# 1_PSU.net
KiCad netlist of a schematic drawn in Altium Designer
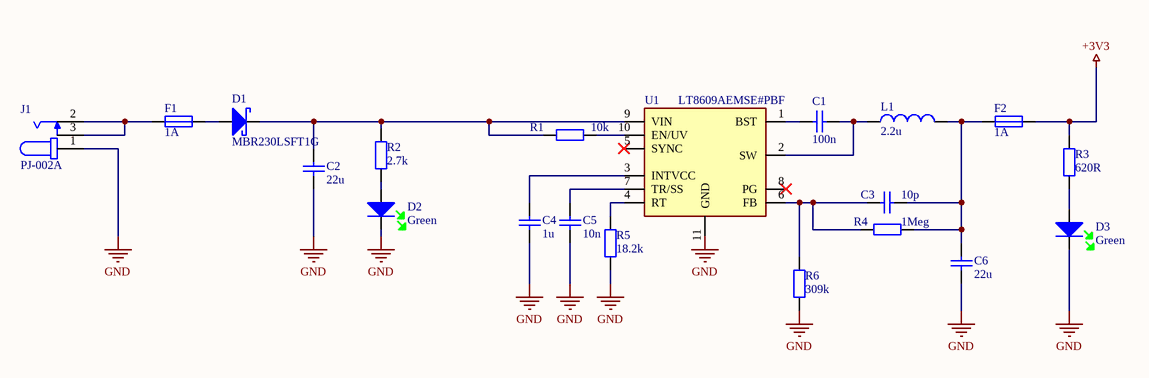
[diagram p0: [1] PSU.SchDoc]

(export (version "E")
  (design (tool "Eeschema 10.0.6"))
  (components
    (comp (ref "C1")
      (value "100n")
      (footprint "STguitar:Capacitor 0603")
      (description "Multilayer Ceramic Capacitors MLCC - SMD/SMT 0603 16VDC 0.1uF 10% X7R")
      (fields
        (field (name "MANUFACTURER PART NUMBER") "EMK107B7104KA-T")
        (field (name "MANUFACTURER") "Taiyo Yuden")
      )
      (libsource (lib "STguitar") (part "Capacitor 100n 10% 0603 EMK107B7104KA-T"))
    )
    (comp (ref "C2")
      (value "22u")
      (footprint "STguitar:Capacitor 0603")
      (description "Multilayer Ceramic Capacitors MLCC - SMD/SMT 22uF+/-20% 16V X5R 1608")
      (fields
        (field (name "MANUFACTURER PART NUMBER") "CL10A226MO7JZNC")
        (field (name "MANUFACTURER") "Samsung Electro-Mechanics")
      )
      (libsource (lib "STguitar") (part "Capacitor 22u 10% 0603 CL10A226MO7JZNC"))
    )
    (comp (ref "C3")
      (value "10p")
      (footprint "STguitar:Capacitor 0603")
      (description "Multilayer Ceramic Capacitors MLCC - SMD/SMT 16V 10pF X7R 0603 10%")
      (fields (field (name "MANUFACTURER PART NUMBER") "0603YC100KAT2A") (field (name "MANUFACTURER") "AVX"))
      (libsource (lib "STguitar") (part "Capacitor 10p 10% 0603 0603YC100KAT2A"))
    )
    (comp (ref "C4")
      (value "1u")
      (footprint "STguitar:Capacitor 0603")
      (description "Multilayer Ceramic Capacitors MLCC - SMD/SMT 0603 16VDC 1uF 10% X7R")
      (fields
        (field (name "MANUFACTURER PART NUMBER") "EMK107B7105KA-T")
        (field (name "MANUFACTURER") "Taiyo Yuden")
      )
      (libsource (lib "STguitar") (part "Capacitor 1u 10% 0603 EMK107B7105KA-T"))
    )
    (comp (ref "C5")
      (value "10n")
      (footprint "STguitar:Capacitor 0603")
      (description "Multilayer Ceramic Capacitors MLCC - SMD/SMT 0603 16VDC 10nF 10% Low Distort")
      (fields
        (field (name "MANUFACTURER PART NUMBER") "EMK107SD103KA-T")
        (field (name "MANUFACTURER") "Taiyo Yuden")
      )
      (libsource (lib "STguitar") (part "Capacitor 10n 10% 0603 EMK107SD103KA-T"))
    )
    (comp (ref "C6")
      (value "22u")
      (footprint "STguitar:Capacitor 0603")
      (description "Multilayer Ceramic Capacitors MLCC - SMD/SMT 22uF+/-20% 16V X5R 1608")
      (fields
        (field (name "MANUFACTURER PART NUMBER") "CL10A226MO7JZNC")
        (field (name "MANUFACTURER") "Samsung Electro-Mechanics")
      )
      (libsource (lib "STguitar") (part "Capacitor 22u 10% 0603 CL10A226MO7JZNC"))
    )
    (comp (ref "D1")
      (value "MBR230LSFT1G")
      (footprint "STguitar:Diode SOD123f")
      (description "Schottky Diodes & Rectifiers 2A 30V SCHOTTKY")
      (fields (field (name "MANUFACTURER") "ON Semiconductor / Fairchild"))
      (libsource (lib "STguitar") (part "Diode Schottky Diodes2A 30V SCHOTTKY MBR230LSFT1G"))
    )
    (comp (ref "D2")
      (value "Green")
      (footprint "STguitar:LED 0805 Green")
      (description "Standard LEDs - SMD 0805 Dome Lens LED Green- 570nm")
      (fields
        (field (name "MANUFACTURER PART NUMBER") "APTD2012LCGCK")
        (field (name "MANUFACTURER") "Kingbright")
      )
      (libsource (lib "STguitar") (part "Diode Standard LEDs - SMD 0805 Dome Lens LED Green- 570nm APTD2012LCGCK"))
    )
    (comp (ref "D3")
      (value "Green")
      (footprint "STguitar:LED 0805 Green")
      (description "Standard LEDs - SMD 0805 Dome Lens LED Green- 570nm")
      (fields
        (field (name "MANUFACTURER PART NUMBER") "APTD2012LCGCK")
        (field (name "MANUFACTURER") "Kingbright")
      )
      (libsource (lib "STguitar") (part "Diode Standard LEDs - SMD 0805 Dome Lens LED Green- 570nm APTD2012LCGCK"))
    )
    (comp (ref "F1")
      (value "1A")
      (footprint "STguitar:Fuse 1206")
      (description "Surface Mount Fuses 1206 SMT Fuse Fast Acting, 1A")
      (fields (field (name "MANUFACTURER PART NUMBER") "C1F 1") (field (name "MANUFACTURER") "Bel Fuse"))
      (libsource (lib "STguitar") (part "Fuse 1206 SMT Fuse Fast Acting, 1A"))
    )
    (comp (ref "F2")
      (value "1A")
      (footprint "STguitar:Fuse 1206")
      (description "Surface Mount Fuses 1206 SMT Fuse Fast Acting, 1A")
      (fields (field (name "MANUFACTURER PART NUMBER") "C1F 1") (field (name "MANUFACTURER") "Bel Fuse"))
      (libsource (lib "STguitar") (part "Fuse 1206 SMT Fuse Fast Acting, 1A"))
    )
    (comp (ref "J1")
      (value "PJ-002A")
      (footprint "STguitar:Mechanical CUI_PJ-002A")
      (description "DC Power Connectors Power Jacks")
      (fields (field (name "MANUFACTURER") "https://pl.mouser.com/datasheet/2/670/pj_002a-1778764.pdf"))
      (libsource (lib "STguitar") (part "Mechanical DC Power Connectors Power Jacks"))
    )
    (comp (ref "L1")
      (value "2.2u")
      (footprint "STguitar:Inductor XAL50xx")
      (description "Fixed Inductors 2.2uH Shld 20% 9.2A 14.5mOhms AECQ2")
      (fields
        (field (name "MANUFACTURER PART NUMBER") "XAL5030-222MEB")
        (field (name "MANUFACTURER") "Coilcraft")
      )
      (libsource (lib "STguitar") (part "Inductor Fixed Inductors 2.2uH Shld 20% 9.2A 14.5mOhms AECQ2"))
    )
    (comp (ref "R1")
      (value "10k")
      (footprint "STguitar:Resistor 0603")
      (description "Thin Film Resistors - SMD 10K ohm 1% 1/10W")
      (fields
        (field (name "MANUFACTURER PART NUMBER") "RT0603FRE0710KL")
        (field (name "MANUFACTURER") "Yageo")
      )
      (libsource (lib "STguitar") (part "Resistor 10k 1% 0603 RT0603FRE0710KL"))
    )
    (comp (ref "R2")
      (value "2.7k")
      (footprint "STguitar:Resistor 0603")
      (description "Thin Film Resistors - SMD 1/10W 2.7K ohm 1% 50ppm")
      (fields
        (field (name "MANUFACTURER PART NUMBER") "RT0603FRE072K7L")
        (field (name "MANUFACTURER") "Yageo")
      )
      (libsource (lib "STguitar") (part "Resistor 2.7k 1% 0603 RT0603FRE072K7L"))
    )
    (comp (ref "R3")
      (value "620R")
      (footprint "STguitar:Resistor 0603")
      (description "Thin Film Resistors - SMD 620 OHM 1% 50PPM 1/10W")
      (fields
        (field (name "MANUFACTURER PART NUMBER") "RT0603FRE07620RL")
        (field (name "MANUFACTURER") "Yageo")
      )
      (libsource (lib "STguitar") (part "Resistor 620R 1% 0603 RT0603FRE07620RL"))
    )
    (comp (ref "R4")
      (value "1Meg")
      (footprint "STguitar:Resistor 0603")
      (description "Thin Film Resistors - SMD 1M OHM 1% 50PPM 1/10W")
      (fields
        (field (name "MANUFACTURER PART NUMBER") "RT0603FRE071ML")
        (field (name "MANUFACTURER") "Yageo")
      )
      (libsource (lib "STguitar") (part "Resistor 1Meg 1% 0603 RT0603FRE071ML"))
    )
    (comp (ref "R5")
      (value "18.2k")
      (footprint "STguitar:Resistor 0603")
      (description "Thin Film Resistors - SMD 1/10W 18.2K ohm 1% 50ppm")
      (fields
        (field (name "MANUFACTURER PART NUMBER") "RT0603FRE0718K2L")
        (field (name "MANUFACTURER") "Yageo")
      )
      (libsource (lib "STguitar") (part "Resistor 18.2k 1% 0603 RT0603FRE0718K2L"))
    )
    (comp (ref "R6")
      (value "309k")
      (footprint "STguitar:Resistor 0603")
      (description "Thin Film Resistors - SMD 1/10W 309K ohm 1% 50ppm")
      (fields
        (field (name "MANUFACTURER PART NUMBER") "RT0603FRE07309KL")
        (field (name "MANUFACTURER") "Yageo")
      )
      (libsource (lib "STguitar") (part "Resistor 309k 1% 0603 RT0603FRE07309KL"))
    )
    (comp (ref "U1")
      (value "LT8609AEMSE#PBF")
      (footprint "STguitar:MSOP-10")
      (description "Switching Voltage Regulators 42V, 2A Synchronous Step-Down Regulator with 2.5uA Quiescent Current")
      (fields (field (name "MANUFACTURER") "Analog Devices"))
      (libsource (lib "STguitar") (part "IC Switching Voltage Regulators 42V, 2A/3A Peak Sync Buck Reg w/ 2.5uA LT8609AEMSE#PBF"))
    )
  )
  (nets
    (net (code "1") (name "+3V3") (class "Default")
      (node (ref "F2") (pin "2") (pinfunction "2_2") (pintype "passive"))
      (node (ref "R3") (pin "2") (pinfunction "2_2") (pintype "passive"))
    )
    (net (code "2") (name "GND") (class "Default")
      (node (ref "C2") (pin "1") (pinfunction "1_1") (pintype "passive"))
      (node (ref "C4") (pin "1") (pinfunction "1_1") (pintype "passive"))
      (node (ref "C5") (pin "1") (pinfunction "1_1") (pintype "passive"))
      (node (ref "C6") (pin "1") (pinfunction "1_1") (pintype "passive"))
      (node (ref "D2") (pin "1") (pinfunction "1_1") (pintype "passive"))
      (node (ref "D3") (pin "1") (pinfunction "1_1") (pintype "passive"))
      (node (ref "J1") (pin "1") (pinfunction "1_1") (pintype "passive"))
      (node (ref "R5") (pin "1") (pinfunction "1_1") (pintype "passive"))
      (node (ref "R6") (pin "1") (pinfunction "1_1") (pintype "passive"))
      (node (ref "U1") (pin "11") (pinfunction "GND_11") (pintype "passive"))
    )
    (net (code "3") (name "Net-(C3-Pad2)") (class "Default")
      (node (ref "C3") (pin "2") (pinfunction "2_2") (pintype "passive"))
      (node (ref "C6") (pin "2") (pinfunction "2_2") (pintype "passive"))
      (node (ref "F2") (pin "1") (pinfunction "1_1") (pintype "passive"))
      (node (ref "L1") (pin "2") (pinfunction "2_2") (pintype "passive"))
      (node (ref "R4") (pin "2") (pinfunction "2_2") (pintype "passive"))
    )
    (net (code "4") (name "Net-(D1-Pad1)") (class "Default")
      (node (ref "D1") (pin "1") (pinfunction "1_1") (pintype "passive"))
      (node (ref "F1") (pin "2") (pinfunction "2_2") (pintype "passive"))
    )
    (net (code "5") (name "Net-(D2-Pad2)") (class "Default")
      (node (ref "D2") (pin "2") (pinfunction "2_2") (pintype "passive"))
      (node (ref "R2") (pin "1") (pinfunction "1_1") (pintype "passive"))
    )
    (net (code "6") (name "Net-(D3-Pad2)") (class "Default")
      (node (ref "D3") (pin "2") (pinfunction "2_2") (pintype "passive"))
      (node (ref "R3") (pin "1") (pinfunction "1_1") (pintype "passive"))
    )
    (net (code "7") (name "Net-(F1-Pad1)") (class "Default")
      (node (ref "F1") (pin "1") (pinfunction "1_1") (pintype "passive"))
      (node (ref "J1") (pin "2") (pinfunction "2_2") (pintype "passive"))
      (node (ref "J1") (pin "3") (pinfunction "3_3") (pintype "passive"))
    )
    (net (code "8") (name "Net-(U1-BST)") (class "Default")
      (node (ref "C1") (pin "1") (pinfunction "1_1") (pintype "passive"))
      (node (ref "U1") (pin "1") (pinfunction "BST_1") (pintype "passive"))
    )
    (net (code "9") (name "Net-(U1-EN{slash}UV)") (class "Default")
      (node (ref "R1") (pin "2") (pinfunction "2_2") (pintype "passive"))
      (node (ref "U1") (pin "10") (pinfunction "EN/UV_10") (pintype "passive"))
    )
    (net (code "10") (name "Net-(U1-FB)") (class "Default")
      (node (ref "C3") (pin "1") (pinfunction "1_1") (pintype "passive"))
      (node (ref "R4") (pin "1") (pinfunction "1_1") (pintype "passive"))
      (node (ref "R6") (pin "2") (pinfunction "2_2") (pintype "passive"))
      (node (ref "U1") (pin "6") (pinfunction "FB_6") (pintype "passive"))
    )
    (net (code "11") (name "Net-(U1-INTVCC)") (class "Default")
      (node (ref "C4") (pin "2") (pinfunction "2_2") (pintype "passive"))
      (node (ref "U1") (pin "3") (pinfunction "INTVCC_3") (pintype "passive"))
    )
    (net (code "12") (name "Net-(U1-RT)") (class "Default")
      (node (ref "R5") (pin "2") (pinfunction "2_2") (pintype "passive"))
      (node (ref "U1") (pin "4") (pinfunction "RT_4") (pintype "passive"))
    )
    (net (code "13") (name "Net-(U1-SW)") (class "Default")
      (node (ref "C1") (pin "2") (pinfunction "2_2") (pintype "passive"))
      (node (ref "L1") (pin "1") (pinfunction "1_1") (pintype "passive"))
      (node (ref "U1") (pin "2") (pinfunction "SW_2") (pintype "passive"))
    )
    (net (code "14") (name "Net-(U1-TR{slash}SS)") (class "Default")
      (node (ref "C5") (pin "2") (pinfunction "2_2") (pintype "passive"))
      (node (ref "U1") (pin "7") (pinfunction "TR/SS_7") (pintype "passive"))
    )
    (net (code "15") (name "Net-(U1-VIN)") (class "Default")
      (node (ref "C2") (pin "2") (pinfunction "2_2") (pintype "passive"))
      (node (ref "D1") (pin "2") (pinfunction "2_2") (pintype "passive"))
      (node (ref "R1") (pin "1") (pinfunction "1_1") (pintype "passive"))
      (node (ref "R2") (pin "2") (pinfunction "2_2") (pintype "passive"))
      (node (ref "U1") (pin "9") (pinfunction "VIN_9") (pintype "passive"))
    )
    (net (code "16") (name "unconnected-(U1-PG-Pad8)") (class "Default")
      (node (ref "U1") (pin "8") (pinfunction "PG_8") (pintype "passive+no_connect"))
    )
    (net (code "17") (name "unconnected-(U1-SYNC-Pad5)") (class "Default")
      (node (ref "U1") (pin "5") (pinfunction "SYNC_5") (pintype "passive+no_connect"))
    )
  )
)
